# molex-header.net
KiCad netlist of a schematic drawn in EAGLE
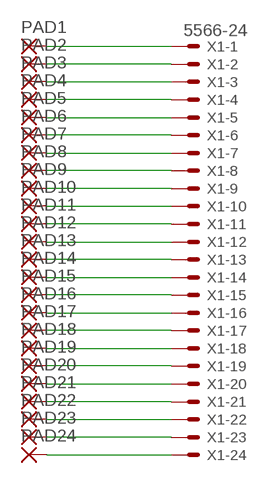
[diagram p0: schematic, sheet 1]

(export (version "E")
  (design (tool "Eeschema 10.0.6"))
  (components
    (comp (ref "PAD1")
      (value "SMD5")
      (footprint "eagle-import:SMD2,54-5,08")
      (libsource (lib "eagle-import") (part "SMD5"))
    )
    (comp (ref "PAD2")
      (value "SMD5")
      (footprint "eagle-import:SMD2,54-5,08")
      (libsource (lib "eagle-import") (part "SMD5"))
    )
    (comp (ref "PAD3")
      (value "SMD5")
      (footprint "eagle-import:SMD2,54-5,08")
      (libsource (lib "eagle-import") (part "SMD5"))
    )
    (comp (ref "PAD4")
      (value "SMD5")
      (footprint "eagle-import:SMD2,54-5,08")
      (libsource (lib "eagle-import") (part "SMD5"))
    )
    (comp (ref "PAD5")
      (value "SMD5")
      (footprint "eagle-import:SMD2,54-5,08")
      (libsource (lib "eagle-import") (part "SMD5"))
    )
    (comp (ref "PAD6")
      (value "SMD5")
      (footprint "eagle-import:SMD2,54-5,08")
      (libsource (lib "eagle-import") (part "SMD5"))
    )
    (comp (ref "PAD7")
      (value "SMD5")
      (footprint "eagle-import:SMD2,54-5,08")
      (libsource (lib "eagle-import") (part "SMD5"))
    )
    (comp (ref "PAD8")
      (value "SMD5")
      (footprint "eagle-import:SMD2,54-5,08")
      (libsource (lib "eagle-import") (part "SMD5"))
    )
    (comp (ref "PAD9")
      (value "SMD5")
      (footprint "eagle-import:SMD2,54-5,08")
      (libsource (lib "eagle-import") (part "SMD5"))
    )
    (comp (ref "PAD10")
      (value "SMD5")
      (footprint "eagle-import:SMD2,54-5,08")
      (libsource (lib "eagle-import") (part "SMD5"))
    )
    (comp (ref "PAD11")
      (value "SMD5")
      (footprint "eagle-import:SMD2,54-5,08")
      (libsource (lib "eagle-import") (part "SMD5"))
    )
    (comp (ref "PAD12")
      (value "SMD5")
      (footprint "eagle-import:SMD2,54-5,08")
      (libsource (lib "eagle-import") (part "SMD5"))
    )
    (comp (ref "PAD13")
      (value "SMD5")
      (footprint "eagle-import:SMD2,54-5,08")
      (libsource (lib "eagle-import") (part "SMD5"))
    )
    (comp (ref "PAD14")
      (value "SMD5")
      (footprint "eagle-import:SMD2,54-5,08")
      (libsource (lib "eagle-import") (part "SMD5"))
    )
    (comp (ref "PAD15")
      (value "SMD5")
      (footprint "eagle-import:SMD2,54-5,08")
      (libsource (lib "eagle-import") (part "SMD5"))
    )
    (comp (ref "PAD16")
      (value "SMD5")
      (footprint "eagle-import:SMD2,54-5,08")
      (libsource (lib "eagle-import") (part "SMD5"))
    )
    (comp (ref "PAD17")
      (value "SMD5")
      (footprint "eagle-import:SMD2,54-5,08")
      (libsource (lib "eagle-import") (part "SMD5"))
    )
    (comp (ref "PAD18")
      (value "SMD5")
      (footprint "eagle-import:SMD2,54-5,08")
      (libsource (lib "eagle-import") (part "SMD5"))
    )
    (comp (ref "PAD19")
      (value "SMD5")
      (footprint "eagle-import:SMD2,54-5,08")
      (libsource (lib "eagle-import") (part "SMD5"))
    )
    (comp (ref "PAD20")
      (value "SMD5")
      (footprint "eagle-import:SMD2,54-5,08")
      (libsource (lib "eagle-import") (part "SMD5"))
    )
    (comp (ref "PAD21")
      (value "SMD5")
      (footprint "eagle-import:SMD2,54-5,08")
      (libsource (lib "eagle-import") (part "SMD5"))
    )
    (comp (ref "PAD22")
      (value "SMD5")
      (footprint "eagle-import:SMD2,54-5,08")
      (libsource (lib "eagle-import") (part "SMD5"))
    )
    (comp (ref "PAD23")
      (value "SMD5")
      (footprint "eagle-import:SMD2,54-5,08")
      (libsource (lib "eagle-import") (part "SMD5"))
    )
    (comp (ref "PAD24")
      (value "SMD5")
      (footprint "eagle-import:SMD2,54-5,08")
      (libsource (lib "eagle-import") (part "SMD5"))
    )
    (comp (ref "X1")
      (value "5566-24")
      (footprint "eagle-import:5566-24")
      (fields (field (name "MF") "MOLEX"))
      (libsource (lib "eagle-import") (part "5566-24"))
    )
  )
  (nets
    (net (code "1") (name "Net-(PAD1-P)") (class "Default")
      (node (ref "PAD1") (pin "1") (pinfunction "P_1") (pintype "passive"))
      (node (ref "X1") (pin "1") (pinfunction "S_1") (pintype "passive"))
    )
    (net (code "2") (name "Net-(PAD2-P)") (class "Default")
      (node (ref "PAD2") (pin "1") (pinfunction "P_1") (pintype "passive"))
      (node (ref "X1") (pin "2") (pinfunction "S_2") (pintype "passive"))
    )
    (net (code "3") (name "Net-(PAD3-P)") (class "Default")
      (node (ref "PAD3") (pin "1") (pinfunction "P_1") (pintype "passive"))
      (node (ref "X1") (pin "3") (pinfunction "S_3") (pintype "passive"))
    )
    (net (code "4") (name "Net-(PAD4-P)") (class "Default")
      (node (ref "PAD4") (pin "1") (pinfunction "P_1") (pintype "passive"))
      (node (ref "X1") (pin "4") (pinfunction "S_4") (pintype "passive"))
    )
    (net (code "5") (name "Net-(PAD5-P)") (class "Default")
      (node (ref "PAD5") (pin "1") (pinfunction "P_1") (pintype "passive"))
      (node (ref "X1") (pin "5") (pinfunction "S_5") (pintype "passive"))
    )
    (net (code "6") (name "Net-(PAD6-P)") (class "Default")
      (node (ref "PAD6") (pin "1") (pinfunction "P_1") (pintype "passive"))
      (node (ref "X1") (pin "6") (pinfunction "S_6") (pintype "passive"))
    )
    (net (code "7") (name "Net-(PAD7-P)") (class "Default")
      (node (ref "PAD7") (pin "1") (pinfunction "P_1") (pintype "passive"))
      (node (ref "X1") (pin "7") (pinfunction "S_7") (pintype "passive"))
    )
    (net (code "8") (name "Net-(PAD8-P)") (class "Default")
      (node (ref "PAD8") (pin "1") (pinfunction "P_1") (pintype "passive"))
      (node (ref "X1") (pin "8") (pinfunction "S_8") (pintype "passive"))
    )
    (net (code "9") (name "Net-(PAD9-P)") (class "Default")
      (node (ref "PAD9") (pin "1") (pinfunction "P_1") (pintype "passive"))
      (node (ref "X1") (pin "9") (pinfunction "S_9") (pintype "passive"))
    )
    (net (code "10") (name "Net-(PAD10-P)") (class "Default")
      (node (ref "PAD10") (pin "1") (pinfunction "P_1") (pintype "passive"))
      (node (ref "X1") (pin "10") (pinfunction "S_10") (pintype "passive"))
    )
    (net (code "11") (name "Net-(PAD11-P)") (class "Default")
      (node (ref "PAD11") (pin "1") (pinfunction "P_1") (pintype "passive"))
      (node (ref "X1") (pin "11") (pinfunction "S_11") (pintype "passive"))
    )
    (net (code "12") (name "Net-(PAD12-P)") (class "Default")
      (node (ref "PAD12") (pin "1") (pinfunction "P_1") (pintype "passive"))
      (node (ref "X1") (pin "12") (pinfunction "S_12") (pintype "passive"))
    )
    (net (code "13") (name "Net-(PAD13-P)") (class "Default")
      (node (ref "PAD13") (pin "1") (pinfunction "P_1") (pintype "passive"))
      (node (ref "X1") (pin "13") (pinfunction "S_13") (pintype "passive"))
    )
    (net (code "14") (name "Net-(PAD14-P)") (class "Default")
      (node (ref "PAD14") (pin "1") (pinfunction "P_1") (pintype "passive"))
      (node (ref "X1") (pin "14") (pinfunction "S_14") (pintype "passive"))
    )
    (net (code "15") (name "Net-(PAD15-P)") (class "Default")
      (node (ref "PAD15") (pin "1") (pinfunction "P_1") (pintype "passive"))
      (node (ref "X1") (pin "15") (pinfunction "S_15") (pintype "passive"))
    )
    (net (code "16") (name "Net-(PAD16-P)") (class "Default")
      (node (ref "PAD16") (pin "1") (pinfunction "P_1") (pintype "passive"))
      (node (ref "X1") (pin "16") (pinfunction "S_16") (pintype "passive"))
    )
    (net (code "17") (name "Net-(PAD17-P)") (class "Default")
      (node (ref "PAD17") (pin "1") (pinfunction "P_1") (pintype "passive"))
      (node (ref "X1") (pin "17") (pinfunction "S_17") (pintype "passive"))
    )
    (net (code "18") (name "Net-(PAD18-P)") (class "Default")
      (node (ref "PAD18") (pin "1") (pinfunction "P_1") (pintype "passive"))
      (node (ref "X1") (pin "18") (pinfunction "S_18") (pintype "passive"))
    )
    (net (code "19") (name "Net-(PAD19-P)") (class "Default")
      (node (ref "PAD19") (pin "1") (pinfunction "P_1") (pintype "passive"))
      (node (ref "X1") (pin "19") (pinfunction "S_19") (pintype "passive"))
    )
    (net (code "20") (name "Net-(PAD20-P)") (class "Default")
      (node (ref "PAD20") (pin "1") (pinfunction "P_1") (pintype "passive"))
      (node (ref "X1") (pin "20") (pinfunction "S_20") (pintype "passive"))
    )
    (net (code "21") (name "Net-(PAD21-P)") (class "Default")
      (node (ref "PAD21") (pin "1") (pinfunction "P_1") (pintype "passive"))
      (node (ref "X1") (pin "21") (pinfunction "S_21") (pintype "passive"))
    )
    (net (code "22") (name "Net-(PAD22-P)") (class "Default")
      (node (ref "PAD22") (pin "1") (pinfunction "P_1") (pintype "passive"))
      (node (ref "X1") (pin "22") (pinfunction "S_22") (pintype "passive"))
    )
    (net (code "23") (name "Net-(PAD23-P)") (class "Default")
      (node (ref "PAD23") (pin "1") (pinfunction "P_1") (pintype "passive"))
      (node (ref "X1") (pin "23") (pinfunction "S_23") (pintype "passive"))
    )
    (net (code "24") (name "Net-(PAD24-P)") (class "Default")
      (node (ref "PAD24") (pin "1") (pinfunction "P_1") (pintype "passive"))
      (node (ref "X1") (pin "24") (pinfunction "S_24") (pintype "passive"))
    )
  )
)
